# weatherstation.net
KiCad netlist of a schematic drawn in EAGLE
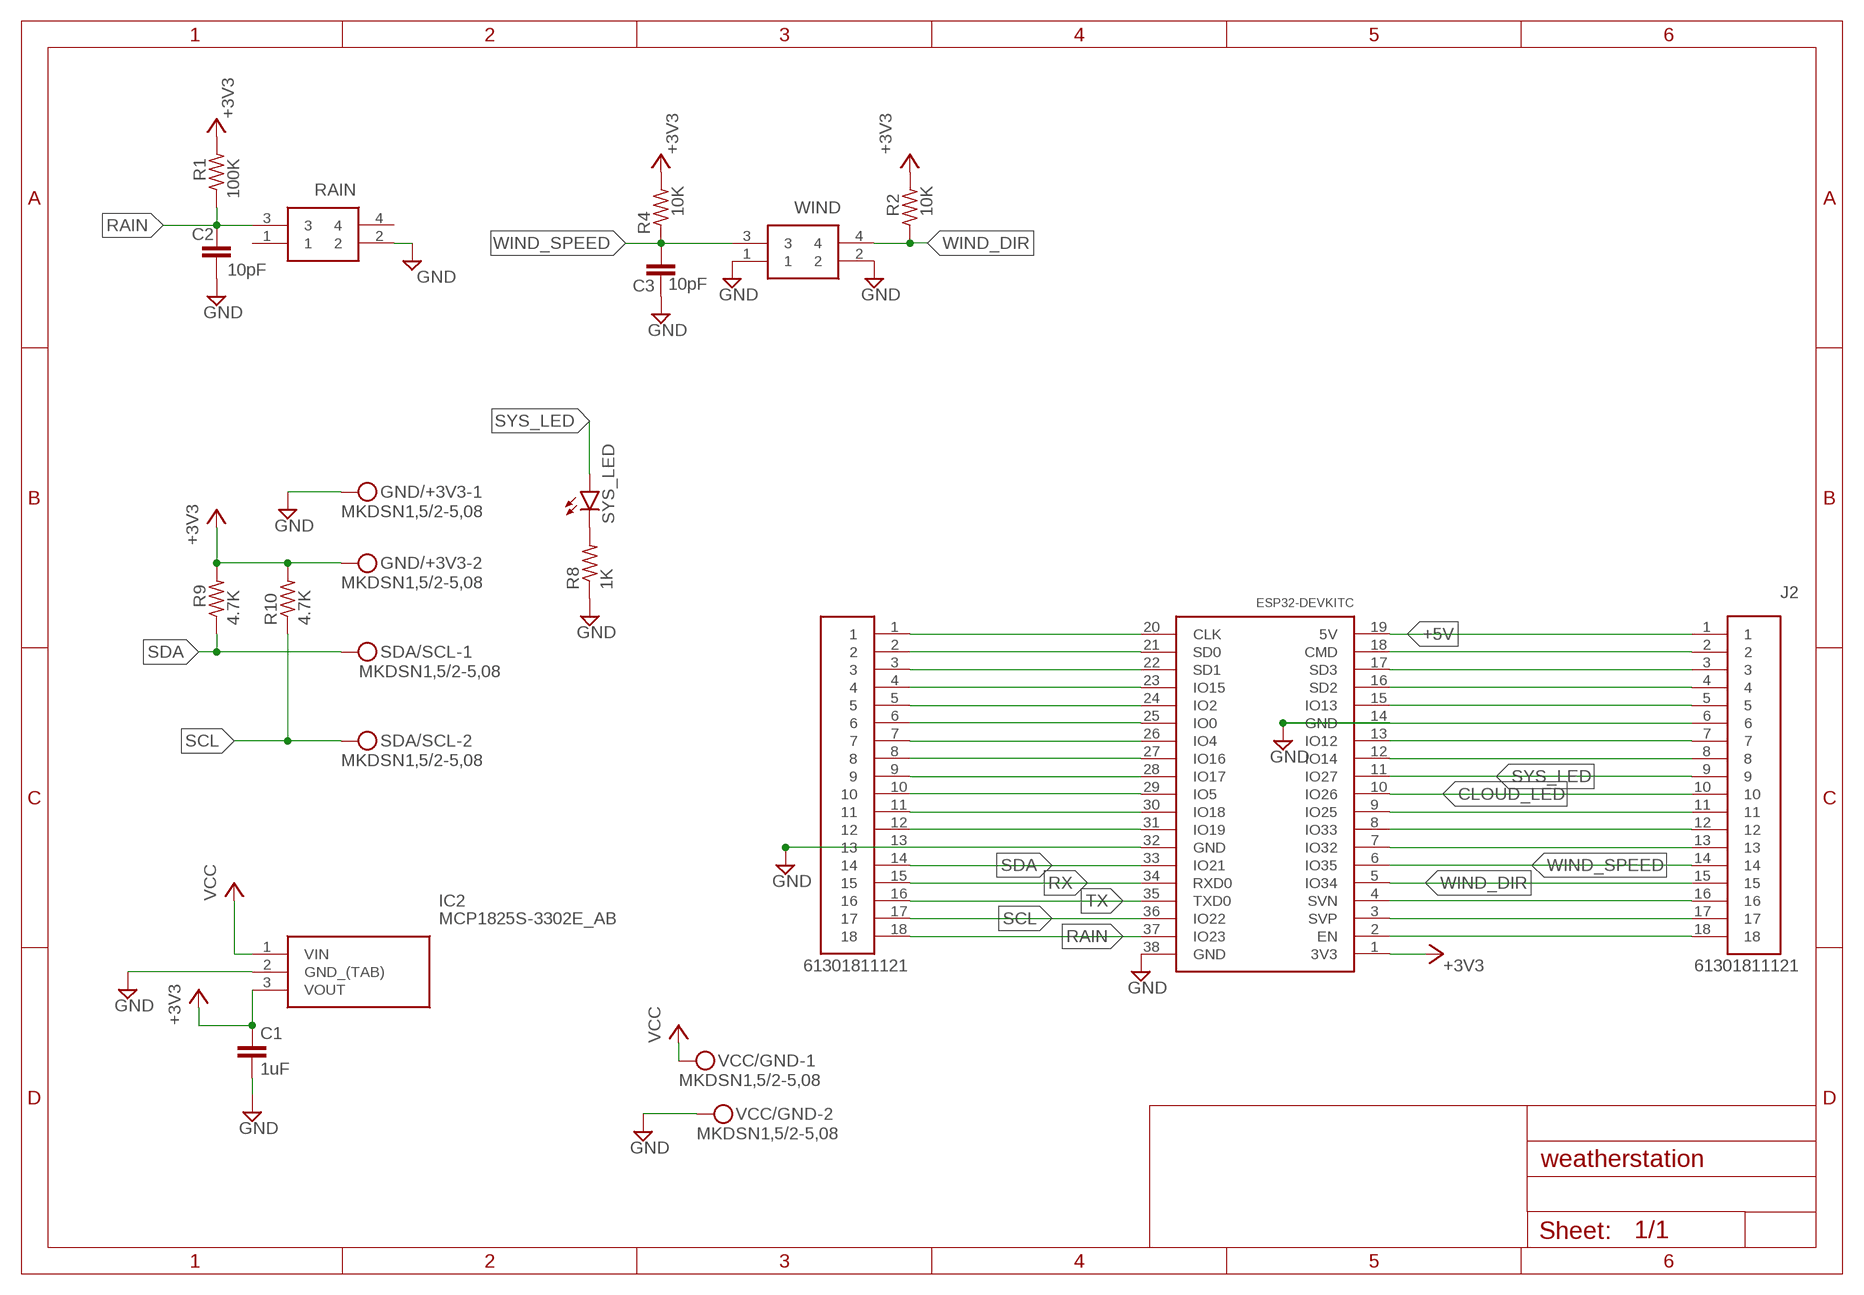
[diagram p0: schematic, sheet 1]

(export (version "E")
  (design (tool "Eeschema 10.0.6"))
  (components
    (comp (ref "C1")
      (value "1uF")
      (footprint "eagle-import:C025-025X050")
      (libsource (lib "eagle-import") (part "C-EU025-025X050"))
    )
    (comp (ref "C2")
      (value "10pF")
      (footprint "eagle-import:C025-025X050")
      (libsource (lib "eagle-import") (part "C-EU025-025X050"))
    )
    (comp (ref "C3")
      (value "10pF")
      (footprint "eagle-import:C025-025X050")
      (libsource (lib "eagle-import") (part "C-EU025-025X050"))
    )
    (comp (ref "GND/+3V3")
      (value "MKDSN1,5/2-5,08")
      (footprint "eagle-import:MKDSN1,5_2-5,08")
      (libsource (lib "eagle-import") (part "MKDSN1,5/2-5,08"))
    )
    (comp (ref "IC2")
      (value "MCP1825S-3302E_AB")
      (footprint "eagle-import:TO254P482X1024X3124-3P")
      (fields
        (field (name "MANUFACTURER_PART_NUMBER") "MCP1825S-3302E/AB")
        (field (name "RS_PART_NUMBER") "6695083P")
      )
      (libsource (lib "eagle-import") (part "MCP1825S-3302E_AB"))
    )
    (comp (ref "J1")
      (value "61301811121")
      (footprint "eagle-import:61301811121")
      (fields
        (field (name "DIGIKEY_PART_NUMBER") "732-5328-ND")
        (field (name "MANUFACTURER") "Wurth Electronics Inc.")
        (field (name "CREATED_BY") "PCBLayout.com")
      )
      (libsource (lib "eagle-import") (part "61301811121"))
    )
    (comp (ref "J2")
      (value "61301811121")
      (footprint "eagle-import:61301811121")
      (fields
        (field (name "DIGIKEY_PART_NUMBER") "732-5328-ND")
        (field (name "MANUFACTURER") "Wurth Electronics Inc.")
        (field (name "CREATED_BY") "PCBLayout.com")
      )
      (libsource (lib "eagle-import") (part "61301811121"))
    )
    (comp (ref "R1")
      (value "100K")
      (footprint "eagle-import:0204_7")
      (libsource (lib "eagle-import") (part "R-US_0204/7"))
    )
    (comp (ref "R2")
      (value "10K")
      (footprint "eagle-import:0204_7")
      (libsource (lib "eagle-import") (part "R-US_0204/7"))
    )
    (comp (ref "R4")
      (value "10K")
      (footprint "eagle-import:0204_7")
      (libsource (lib "eagle-import") (part "R-US_0204/7"))
    )
    (comp (ref "R8")
      (value "1K")
      (footprint "eagle-import:0204_7")
      (libsource (lib "eagle-import") (part "R-US_0204/7"))
    )
    (comp (ref "R9")
      (value "4.7K")
      (footprint "eagle-import:0204_7")
      (libsource (lib "eagle-import") (part "R-US_0204/7"))
    )
    (comp (ref "R10")
      (value "4.7K")
      (footprint "eagle-import:0204_7")
      (libsource (lib "eagle-import") (part "R-US_0204/7"))
    )
    (comp (ref "RAIN")
      (value "TM5RU1-64_50_")
      (footprint "eagle-import:TM5RU16450")
      (fields
        (field (name "MANUFACTURER_PART_NUMBER") "TM5RU1-64(50)")
        (field (name "RS_PART_NUMBER") "7644828")
      )
      (libsource (lib "eagle-import") (part "TM5RU1-64_50_"))
    )
    (comp (ref "SDA/SCL")
      (value "MKDSN1,5/2-5,08")
      (footprint "eagle-import:MKDSN1,5_2-5,08")
      (libsource (lib "eagle-import") (part "MKDSN1,5/2-5,08"))
    )
    (comp (ref "SYS_LED")
      (value "LED5MM")
      (footprint "eagle-import:LED5MM")
      (libsource (lib "eagle-import") (part "LED5MM"))
    )
    (comp (ref "U$1")
      (value "ESP32DEVKITC")
      (footprint "eagle-import:ESP32-DEVKITC")
      (libsource (lib "eagle-import") (part "ESP32DEVKITC"))
    )
    (comp (ref "VCC/GND")
      (value "MKDSN1,5/2-5,08")
      (footprint "eagle-import:MKDSN1,5_2-5,08")
      (libsource (lib "eagle-import") (part "MKDSN1,5/2-5,08"))
    )
    (comp (ref "WIND")
      (value "TM5RU1-64_50_")
      (footprint "eagle-import:TM5RU16450")
      (fields
        (field (name "MANUFACTURER_PART_NUMBER") "TM5RU1-64(50)")
        (field (name "RS_PART_NUMBER") "7644828")
      )
      (libsource (lib "eagle-import") (part "TM5RU1-64_50_"))
    )
  )
  (nets
    (net (code "1") (name "+3V3") (class "Default")
      (node (ref "C1") (pin "1") (pinfunction "1_1") (pintype "passive"))
      (node (ref "GND/+3V3") (pin "2") (pinfunction "KL_2") (pintype "passive"))
      (node (ref "IC2") (pin "3") (pinfunction "VOUT_3") (pintype "bidirectional"))
      (node (ref "R1") (pin "2") (pinfunction "2_2") (pintype "passive"))
      (node (ref "R10") (pin "2") (pinfunction "2_2") (pintype "passive"))
      (node (ref "R2") (pin "2") (pinfunction "2_2") (pintype "passive"))
      (node (ref "R4") (pin "2") (pinfunction "2_2") (pintype "passive"))
      (node (ref "R9") (pin "2") (pinfunction "2_2") (pintype "passive"))
      (node (ref "U$1") (pin "1") (pinfunction "3V3_1") (pintype "bidirectional"))
    )
    (net (code "2") (name "+5V") (class "Default")
      (node (ref "J2") (pin "1") (pinfunction "1_1") (pintype "passive"))
      (node (ref "U$1") (pin "19") (pinfunction "5V_19") (pintype "bidirectional"))
    )
    (net (code "3") (name "CLOUD_LED") (class "Default")
      (node (ref "J2") (pin "10") (pinfunction "10_10") (pintype "passive"))
      (node (ref "U$1") (pin "10") (pinfunction "IO26_10") (pintype "bidirectional"))
    )
    (net (code "4") (name "GND") (class "Default")
      (node (ref "C1") (pin "2") (pinfunction "2_2") (pintype "passive"))
      (node (ref "C2") (pin "2") (pinfunction "2_2") (pintype "passive"))
      (node (ref "C3") (pin "2") (pinfunction "2_2") (pintype "passive"))
      (node (ref "GND/+3V3") (pin "1") (pinfunction "KL_1") (pintype "passive"))
      (node (ref "IC2") (pin "2") (pinfunction "GND_(TAB)_2") (pintype "bidirectional"))
      (node (ref "J1") (pin "13") (pinfunction "13_13") (pintype "passive"))
      (node (ref "J2") (pin "6") (pinfunction "6_6") (pintype "passive"))
      (node (ref "R8") (pin "1") (pinfunction "1_1") (pintype "passive"))
      (node (ref "RAIN") (pin "2") (pinfunction "2_2") (pintype "bidirectional"))
      (node (ref "U$1") (pin "14") (pinfunction "GND_14") (pintype "bidirectional"))
      (node (ref "U$1") (pin "32") (pinfunction "GND_32") (pintype "bidirectional"))
      (node (ref "U$1") (pin "38") (pinfunction "GND_38") (pintype "bidirectional"))
      (node (ref "VCC/GND") (pin "2") (pinfunction "KL_2") (pintype "passive"))
      (node (ref "WIND") (pin "1") (pinfunction "1_1") (pintype "bidirectional"))
      (node (ref "WIND") (pin "2") (pinfunction "2_2") (pintype "bidirectional"))
    )
    (net (code "5") (name "Net-(SYS_LED-C)") (class "Default")
      (node (ref "R8") (pin "2") (pinfunction "2_2") (pintype "passive"))
      (node (ref "SYS_LED") (pin "K") (pinfunction "C_K") (pintype "passive"))
    )
    (net (code "6") (name "Net-(U$1-CLK)") (class "Default")
      (node (ref "J1") (pin "1") (pinfunction "1_1") (pintype "passive"))
      (node (ref "U$1") (pin "20") (pinfunction "CLK_20") (pintype "bidirectional"))
    )
    (net (code "7") (name "Net-(U$1-CMD)") (class "Default")
      (node (ref "J2") (pin "2") (pinfunction "2_2") (pintype "passive"))
      (node (ref "U$1") (pin "18") (pinfunction "CMD_18") (pintype "bidirectional"))
    )
    (net (code "8") (name "Net-(U$1-EN)") (class "Default")
      (node (ref "J2") (pin "18") (pinfunction "18_18") (pintype "passive"))
      (node (ref "U$1") (pin "2") (pinfunction "EN_2") (pintype "bidirectional"))
    )
    (net (code "9") (name "Net-(U$1-IO0)") (class "Default")
      (node (ref "J1") (pin "6") (pinfunction "6_6") (pintype "passive"))
      (node (ref "U$1") (pin "25") (pinfunction "IO0_25") (pintype "bidirectional"))
    )
    (net (code "10") (name "Net-(U$1-IO2)") (class "Default")
      (node (ref "J1") (pin "5") (pinfunction "5_5") (pintype "passive"))
      (node (ref "U$1") (pin "24") (pinfunction "IO2_24") (pintype "bidirectional"))
    )
    (net (code "11") (name "Net-(U$1-IO4)") (class "Default")
      (node (ref "J1") (pin "7") (pinfunction "7_7") (pintype "passive"))
      (node (ref "U$1") (pin "26") (pinfunction "IO4_26") (pintype "bidirectional"))
    )
    (net (code "12") (name "Net-(U$1-IO5)") (class "Default")
      (node (ref "J1") (pin "10") (pinfunction "10_10") (pintype "passive"))
      (node (ref "U$1") (pin "29") (pinfunction "IO5_29") (pintype "bidirectional"))
    )
    (net (code "13") (name "Net-(U$1-IO12)") (class "Default")
      (node (ref "J2") (pin "7") (pinfunction "7_7") (pintype "passive"))
      (node (ref "U$1") (pin "13") (pinfunction "IO12_13") (pintype "bidirectional"))
    )
    (net (code "14") (name "Net-(U$1-IO13)") (class "Default")
      (node (ref "J2") (pin "5") (pinfunction "5_5") (pintype "passive"))
      (node (ref "U$1") (pin "15") (pinfunction "IO13_15") (pintype "bidirectional"))
    )
    (net (code "15") (name "Net-(U$1-IO14)") (class "Default")
      (node (ref "J2") (pin "8") (pinfunction "8_8") (pintype "passive"))
      (node (ref "U$1") (pin "12") (pinfunction "IO14_12") (pintype "bidirectional"))
    )
    (net (code "16") (name "Net-(U$1-IO15)") (class "Default")
      (node (ref "J1") (pin "4") (pinfunction "4_4") (pintype "passive"))
      (node (ref "U$1") (pin "23") (pinfunction "IO15_23") (pintype "bidirectional"))
    )
    (net (code "17") (name "Net-(U$1-IO16)") (class "Default")
      (node (ref "J1") (pin "8") (pinfunction "8_8") (pintype "passive"))
      (node (ref "U$1") (pin "27") (pinfunction "IO16_27") (pintype "bidirectional"))
    )
    (net (code "18") (name "Net-(U$1-IO17)") (class "Default")
      (node (ref "J1") (pin "9") (pinfunction "9_9") (pintype "passive"))
      (node (ref "U$1") (pin "28") (pinfunction "IO17_28") (pintype "bidirectional"))
    )
    (net (code "19") (name "Net-(U$1-IO18)") (class "Default")
      (node (ref "J1") (pin "11") (pinfunction "11_11") (pintype "passive"))
      (node (ref "U$1") (pin "30") (pinfunction "IO18_30") (pintype "bidirectional"))
    )
    (net (code "20") (name "Net-(U$1-IO19)") (class "Default")
      (node (ref "J1") (pin "12") (pinfunction "12_12") (pintype "passive"))
      (node (ref "U$1") (pin "31") (pinfunction "IO19_31") (pintype "bidirectional"))
    )
    (net (code "21") (name "Net-(U$1-IO25)") (class "Default")
      (node (ref "J2") (pin "11") (pinfunction "11_11") (pintype "passive"))
      (node (ref "U$1") (pin "9") (pinfunction "IO25_9") (pintype "bidirectional"))
    )
    (net (code "22") (name "Net-(U$1-IO32)") (class "Default")
      (node (ref "J2") (pin "13") (pinfunction "13_13") (pintype "passive"))
      (node (ref "U$1") (pin "7") (pinfunction "IO32_7") (pintype "bidirectional"))
    )
    (net (code "23") (name "Net-(U$1-IO33)") (class "Default")
      (node (ref "J2") (pin "12") (pinfunction "12_12") (pintype "passive"))
      (node (ref "U$1") (pin "8") (pinfunction "IO33_8") (pintype "bidirectional"))
    )
    (net (code "24") (name "Net-(U$1-SD0)") (class "Default")
      (node (ref "J1") (pin "2") (pinfunction "2_2") (pintype "passive"))
      (node (ref "U$1") (pin "21") (pinfunction "SD0_21") (pintype "bidirectional"))
    )
    (net (code "25") (name "Net-(U$1-SD1)") (class "Default")
      (node (ref "J1") (pin "3") (pinfunction "3_3") (pintype "passive"))
      (node (ref "U$1") (pin "22") (pinfunction "SD1_22") (pintype "bidirectional"))
    )
    (net (code "26") (name "Net-(U$1-SD2)") (class "Default")
      (node (ref "J2") (pin "4") (pinfunction "4_4") (pintype "passive"))
      (node (ref "U$1") (pin "16") (pinfunction "SD2_16") (pintype "bidirectional"))
    )
    (net (code "27") (name "Net-(U$1-SD3)") (class "Default")
      (node (ref "J2") (pin "3") (pinfunction "3_3") (pintype "passive"))
      (node (ref "U$1") (pin "17") (pinfunction "SD3_17") (pintype "bidirectional"))
    )
    (net (code "28") (name "Net-(U$1-SVN)") (class "Default")
      (node (ref "J2") (pin "16") (pinfunction "16_16") (pintype "passive"))
      (node (ref "U$1") (pin "4") (pinfunction "SVN_4") (pintype "bidirectional"))
    )
    (net (code "29") (name "Net-(U$1-SVP)") (class "Default")
      (node (ref "J2") (pin "17") (pinfunction "17_17") (pintype "passive"))
      (node (ref "U$1") (pin "3") (pinfunction "SVP_3") (pintype "bidirectional"))
    )
    (net (code "30") (name "RAIN") (class "Default")
      (node (ref "C2") (pin "1") (pinfunction "1_1") (pintype "passive"))
      (node (ref "J1") (pin "18") (pinfunction "18_18") (pintype "passive"))
      (node (ref "R1") (pin "1") (pinfunction "1_1") (pintype "passive"))
      (node (ref "RAIN") (pin "3") (pinfunction "3_3") (pintype "bidirectional"))
      (node (ref "U$1") (pin "37") (pinfunction "IO23_37") (pintype "bidirectional"))
    )
    (net (code "31") (name "RX") (class "Default")
      (node (ref "J1") (pin "15") (pinfunction "15_15") (pintype "passive"))
      (node (ref "U$1") (pin "34") (pinfunction "RXD0_34") (pintype "bidirectional"))
    )
    (net (code "32") (name "SCL") (class "Default")
      (node (ref "J1") (pin "17") (pinfunction "17_17") (pintype "passive"))
      (node (ref "R10") (pin "1") (pinfunction "1_1") (pintype "passive"))
      (node (ref "SDA/SCL") (pin "2") (pinfunction "KL_2") (pintype "passive"))
      (node (ref "U$1") (pin "36") (pinfunction "IO22_36") (pintype "bidirectional"))
    )
    (net (code "33") (name "SDA") (class "Default")
      (node (ref "J1") (pin "14") (pinfunction "14_14") (pintype "passive"))
      (node (ref "R9") (pin "1") (pinfunction "1_1") (pintype "passive"))
      (node (ref "SDA/SCL") (pin "1") (pinfunction "KL_1") (pintype "passive"))
      (node (ref "U$1") (pin "33") (pinfunction "IO21_33") (pintype "bidirectional"))
    )
    (net (code "34") (name "SYS_LED") (class "Default")
      (node (ref "J2") (pin "9") (pinfunction "9_9") (pintype "passive"))
      (node (ref "SYS_LED") (pin "A") (pinfunction "A_A") (pintype "passive"))
      (node (ref "U$1") (pin "11") (pinfunction "IO27_11") (pintype "bidirectional"))
    )
    (net (code "35") (name "TX") (class "Default")
      (node (ref "J1") (pin "16") (pinfunction "16_16") (pintype "passive"))
      (node (ref "U$1") (pin "35") (pinfunction "TXD0_35") (pintype "bidirectional"))
    )
    (net (code "36") (name "VCC") (class "Default")
      (node (ref "IC2") (pin "1") (pinfunction "VIN_1") (pintype "bidirectional"))
      (node (ref "VCC/GND") (pin "1") (pinfunction "KL_1") (pintype "passive"))
    )
    (net (code "37") (name "WIND_DIR") (class "Default")
      (node (ref "J2") (pin "15") (pinfunction "15_15") (pintype "passive"))
      (node (ref "R2") (pin "1") (pinfunction "1_1") (pintype "passive"))
      (node (ref "U$1") (pin "5") (pinfunction "IO34_5") (pintype "bidirectional"))
      (node (ref "WIND") (pin "4") (pinfunction "4_4") (pintype "bidirectional"))
    )
    (net (code "38") (name "WIND_SPEED") (class "Default")
      (node (ref "C3") (pin "1") (pinfunction "1_1") (pintype "passive"))
      (node (ref "J2") (pin "14") (pinfunction "14_14") (pintype "passive"))
      (node (ref "R4") (pin "1") (pinfunction "1_1") (pintype "passive"))
      (node (ref "U$1") (pin "6") (pinfunction "IO35_6") (pintype "bidirectional"))
      (node (ref "WIND") (pin "3") (pinfunction "3_3") (pintype "bidirectional"))
    )
    (net (code "39") (name "unconnected-(RAIN-Pad1)") (class "Default")
      (node (ref "RAIN") (pin "1") (pinfunction "1_1") (pintype "bidirectional"))
    )
    (net (code "40") (name "unconnected-(RAIN-Pad4)") (class "Default")
      (node (ref "RAIN") (pin "4") (pinfunction "4_4") (pintype "bidirectional"))
    )
  )
)
